# TheConductorChildBoardV2.net
KiCad netlist of a schematic drawn in Altium Designer
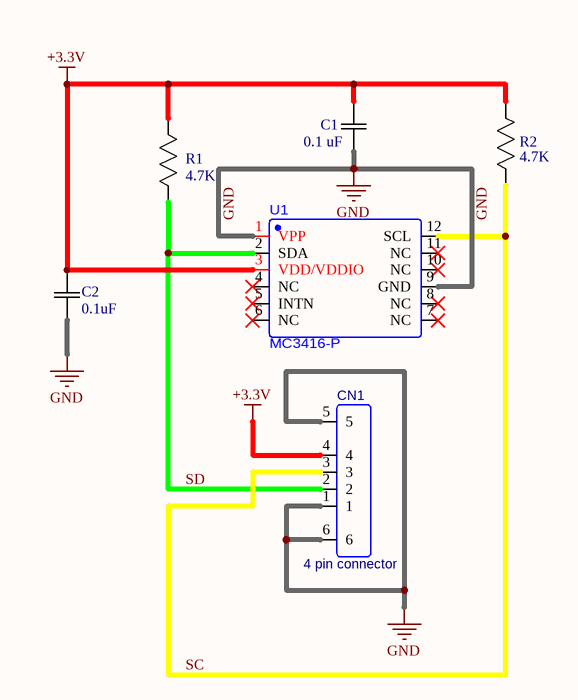
[diagram p0: TheConductorChildBoardV2.SchDoc]

(export (version "E")
  (design (tool "Eeschema 10.0.6"))
  (components
    (comp (ref "C1")
      (value "0.1 uF")
      (footprint "CAP_AMK107BJ475MK-T_TAY")
      (description "SMT Capacitor 0.1 uF")
      (fields
        (field (name "MANUFACTURER_PART_NUMBER") "AMK107BJ475MK-T")
        (field (name "LCSC PART #") "C1591")
        (field (name "COPYRIGHT") "Copyright (C) 2023 Ultra Librarian. All rights reserved.")
      )
      (libsource (lib "TheConductor-ChildBoard") (part "CL10B104KB8NNNC"))
    )
    (comp (ref "C2")
      (value "0.1uF")
      (footprint "CAP_AMK107BJ475MK-T_TAY")
      (description "SMT Capacitor 0.1 uF")
      (fields
        (field (name "MANUFACTURER_PART_NUMBER") "AMK107BJ475MK-T")
        (field (name "LCSC PART #") "C1591")
        (field (name "COPYRIGHT") "Copyright (C) 2023 Ultra Librarian. All rights reserved.")
      )
      (libsource (lib "The conductor") (part "CL10B104KB8NNNC"))
    )
    (comp (ref "CN1")
      (value "4 pin connector")
      (footprint "CONN-SMD_4P-P1.00_SM04B-SRSS-TB-LF-SN - duplicate")
      (fields
        (field (name "MANUFACTURER") "JST")
        (field (name "MANUFACTURER PART") "SM04B-SRSS-TB(LF)(SN)")
        (field (name "LCSC PART #") "C160404")
        (field (name "CONTRIBUTOR") "LCSC")
      )
      (libsource (lib "TheConductor-ChildBoard") (part "SM04B-SRSS-TB (LF)(SN)"))
    )
    (comp (ref "R1")
      (value "4.7K")
      (footprint "RC0603N_YAG")
      (description "SMT Resitor 4.7k")
      (fields
        (field (name "MANUFACTURER_PART_NUMBER") "RC0603JR-072K7L")
        (field (name "LCSC PART #") "C105428")
        (field (name "COPYRIGHT") "Copyright (C) 2023 Ultra Librarian. All rights reserved.")
      )
      (libsource (lib "TheConductor-ChildBoard") (part "RC0603JR-074K7L"))
    )
    (comp (ref "R2")
      (value "4.7K")
      (footprint "RC0603N_YAG")
      (description "SMT Resitor 4.7k")
      (fields
        (field (name "MANUFACTURER_PART_NUMBER") "RC0603JR-072K7L")
        (field (name "LCSC PART #") "C105428")
        (field (name "COPYRIGHT") "Copyright (C) 2023 Ultra Librarian. All rights reserved.")
      )
      (libsource (lib "TheConductor-ChildBoard") (part "RC0603JR-074K7L"))
    )
    (comp (ref "U1")
      (value "MC3416-P")
      (footprint "LGA-12_L2.0-W2.0-P0.50-BL - duplicate")
      (description "VLGA-12 Attitude Sensor/Gyroscope ROHS")
      (fields (field (name "LCSC PART #") "C5250287"))
      (libsource (lib "TheConductor-ChildBoard") (part "MC3416-P"))
    )
  )
  (nets
    (net (code "1") (name "+3.3V") (class "Default")
      (node (ref "C1") (pin "2") (pinfunction "2_2") (pintype "passive"))
      (node (ref "C2") (pin "1") (pinfunction "1_1") (pintype "passive"))
      (node (ref "CN1") (pin "4") (pinfunction "4_4") (pintype "passive"))
      (node (ref "R1") (pin "1") (pinfunction "1_1") (pintype "passive"))
      (node (ref "R2") (pin "1") (pinfunction "1_1") (pintype "passive"))
      (node (ref "U1") (pin "3") (pinfunction "VDD/VDDIO_3") (pintype "passive"))
    )
    (net (code "2") (name "/SC") (class "Default")
      (node (ref "CN1") (pin "3") (pinfunction "3_3") (pintype "passive"))
      (node (ref "R2") (pin "2") (pinfunction "2_2") (pintype "passive"))
      (node (ref "U1") (pin "12") (pinfunction "SCL_12") (pintype "passive"))
    )
    (net (code "3") (name "/SD") (class "Default")
      (node (ref "CN1") (pin "2") (pinfunction "2_2") (pintype "passive"))
      (node (ref "R1") (pin "2") (pinfunction "2_2") (pintype "passive"))
      (node (ref "U1") (pin "2") (pinfunction "SDA_2") (pintype "passive"))
    )
    (net (code "4") (name "GND") (class "Default")
      (node (ref "C1") (pin "1") (pinfunction "1_1") (pintype "passive"))
      (node (ref "C2") (pin "2") (pinfunction "2_2") (pintype "passive"))
      (node (ref "CN1") (pin "1") (pinfunction "1_1") (pintype "passive"))
      (node (ref "CN1") (pin "5") (pinfunction "5_5") (pintype "passive"))
      (node (ref "CN1") (pin "6") (pinfunction "6_6") (pintype "passive"))
      (node (ref "U1") (pin "1") (pinfunction "VPP_1") (pintype "passive"))
      (node (ref "U1") (pin "9") (pinfunction "GND_9") (pintype "passive"))
    )
    (net (code "5") (name "unconnected-(U1-INTN-Pad5)") (class "Default")
      (node (ref "U1") (pin "5") (pinfunction "INTN_5") (pintype "passive+no_connect"))
    )
    (net (code "6") (name "unconnected-(U1-NC-Pad4)") (class "Default")
      (node (ref "U1") (pin "4") (pinfunction "NC_4") (pintype "passive+no_connect"))
    )
    (net (code "7") (name "unconnected-(U1-NC-Pad6)") (class "Default")
      (node (ref "U1") (pin "6") (pinfunction "NC_6") (pintype "passive+no_connect"))
    )
    (net (code "8") (name "unconnected-(U1-NC-Pad7)") (class "Default")
      (node (ref "U1") (pin "7") (pinfunction "NC_7") (pintype "passive+no_connect"))
    )
    (net (code "9") (name "unconnected-(U1-NC-Pad8)") (class "Default")
      (node (ref "U1") (pin "8") (pinfunction "NC_8") (pintype "passive+no_connect"))
    )
    (net (code "10") (name "unconnected-(U1-NC-Pad10)") (class "Default")
      (node (ref "U1") (pin "10") (pinfunction "NC_10") (pintype "passive+no_connect"))
    )
    (net (code "11") (name "unconnected-(U1-NC-Pad11)") (class "Default")
      (node (ref "U1") (pin "11") (pinfunction "NC_11") (pintype "passive+no_connect"))
    )
  )
)
